# Arduino_Shield.net
KiCad netlist of a schematic drawn in EAGLE
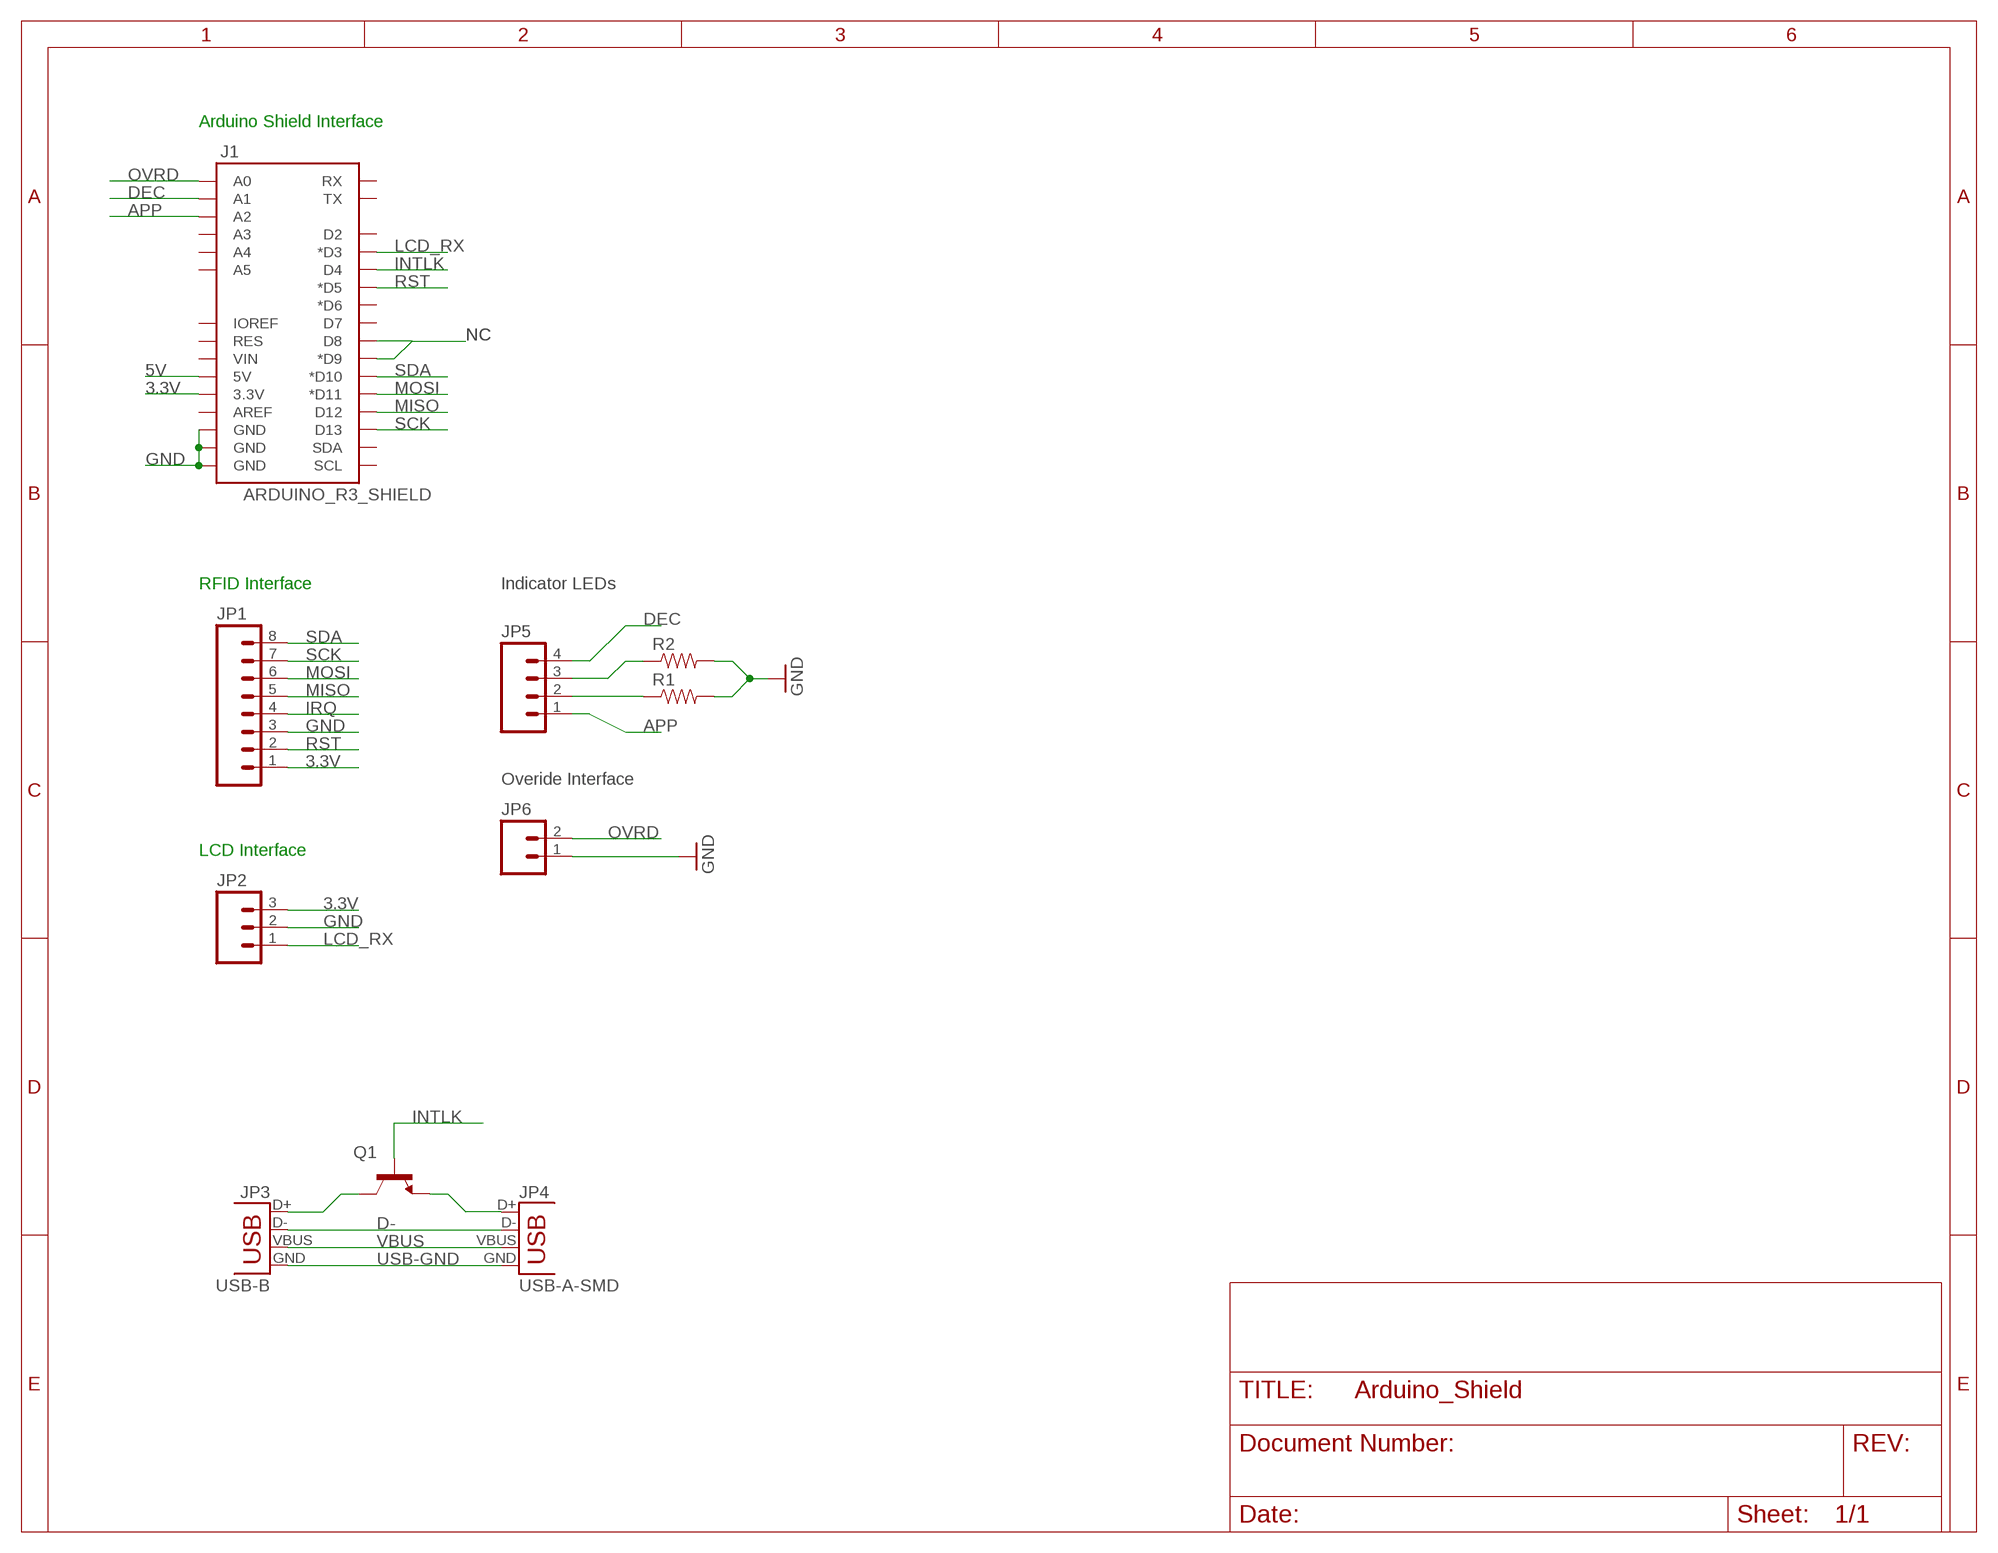
[diagram p0: schematic, sheet 1]

(export (version "E")
  (design (tool "Eeschema 10.0.6"))
  (components
    (comp (ref "J1")
      (value "ARDUINO_R3_SHIELD")
      (footprint "eagle-import:UNO_R3_SHIELD")
      (libsource (lib "eagle-import") (part "ARDUINO_R3_SHIELD"))
    )
    (comp (ref "JP1")
      (value "M08LONGPADS")
      (footprint "eagle-import:1X08_LONGPADS")
      (libsource (lib "eagle-import") (part "M08LONGPADS"))
    )
    (comp (ref "JP2")
      (value "M03LONGPADS")
      (footprint "eagle-import:1X03_LONGPADS")
      (libsource (lib "eagle-import") (part "M03LONGPADS"))
    )
    (comp (ref "JP3")
      (value "USB-B")
      (footprint "eagle-import:USB-B-PTH")
      (libsource (lib "eagle-import") (part "USBPTH"))
    )
    (comp (ref "JP4")
      (value "USB-A-SMD")
      (footprint "eagle-import:USB-A-S-NOSILK-FEMALE")
      (libsource (lib "eagle-import") (part "USB-A-SMD"))
    )
    (comp (ref "JP5")
      (value "M04LONGPADS")
      (footprint "eagle-import:1X04_LONGPADS")
      (libsource (lib "eagle-import") (part "M04LONGPADS"))
    )
    (comp (ref "JP6")
      (value "M02LOCK_LONGPADS")
      (footprint "eagle-import:1X02_LOCK_LONGPADS")
      (libsource (lib "eagle-import") (part "M02LOCK_LONGPADS"))
    )
    (comp (ref "Q1")
      (value "TRANSISTOR_NPNBC547")
      (footprint "eagle-import:TO-92-AMMO")
      (libsource (lib "eagle-import") (part "TRANSISTOR_NPNBC547"))
    )
    (comp (ref "R1")
      (value "RESISTORPTH-1/4W")
      (footprint "eagle-import:AXIAL-0.4")
      (libsource (lib "eagle-import") (part "RESISTORPTH-1/4W"))
    )
    (comp (ref "R2")
      (value "RESISTORPTH-1/4W")
      (footprint "eagle-import:AXIAL-0.4")
      (libsource (lib "eagle-import") (part "RESISTORPTH-1/4W"))
    )
  )
  (nets
    (net (code "1") (name "/3.3V") (class "Default")
      (node (ref "J1") (pin "3.3V") (pinfunction "3.3V_3.3V") (pintype "bidirectional"))
      (node (ref "JP1") (pin "1") (pinfunction "1_1") (pintype "passive"))
      (node (ref "JP2") (pin "3") (pinfunction "3_3") (pintype "passive"))
    )
    (net (code "2") (name "/5V") (class "Default")
      (node (ref "J1") (pin "5V") (pinfunction "5V_5V") (pintype "bidirectional"))
    )
    (net (code "3") (name "/APP") (class "Default")
      (node (ref "J1") (pin "A2") (pinfunction "A2_A2") (pintype "bidirectional"))
      (node (ref "JP5") (pin "1") (pinfunction "1_1") (pintype "passive"))
    )
    (net (code "4") (name "/D-") (class "Default")
      (node (ref "JP3") (pin "D-") (pinfunction "D-_D-") (pintype "bidirectional"))
      (node (ref "JP4") (pin "D-") (pinfunction "D-_D-") (pintype "bidirectional"))
    )
    (net (code "5") (name "/DEC") (class "Default")
      (node (ref "J1") (pin "A1") (pinfunction "A1_A1") (pintype "bidirectional"))
      (node (ref "JP5") (pin "4") (pinfunction "4_4") (pintype "passive"))
    )
    (net (code "6") (name "/INTLK") (class "Default")
      (node (ref "J1") (pin "D4") (pinfunction "D4_D4") (pintype "bidirectional"))
      (node (ref "Q1") (pin "2") (pinfunction "B_2") (pintype "passive"))
    )
    (net (code "7") (name "/IRQ") (class "Default")
      (node (ref "JP1") (pin "4") (pinfunction "4_4") (pintype "passive"))
    )
    (net (code "8") (name "/LCD_RX") (class "Default")
      (node (ref "J1") (pin "D3") (pinfunction "*D3_D3") (pintype "bidirectional"))
      (node (ref "JP2") (pin "1") (pinfunction "1_1") (pintype "passive"))
    )
    (net (code "9") (name "/MISO") (class "Default")
      (node (ref "J1") (pin "D12") (pinfunction "D12_D12") (pintype "bidirectional"))
      (node (ref "JP1") (pin "5") (pinfunction "5_5") (pintype "passive"))
    )
    (net (code "10") (name "/MOSI") (class "Default")
      (node (ref "J1") (pin "D11") (pinfunction "*D11_D11") (pintype "bidirectional"))
      (node (ref "JP1") (pin "6") (pinfunction "6_6") (pintype "passive"))
    )
    (net (code "11") (name "/OVRD") (class "Default")
      (node (ref "J1") (pin "A0") (pinfunction "A0_A0") (pintype "bidirectional"))
      (node (ref "JP6") (pin "2") (pinfunction "2_2") (pintype "passive"))
    )
    (net (code "12") (name "/RST") (class "Default")
      (node (ref "J1") (pin "D5") (pinfunction "*D5_D5") (pintype "bidirectional"))
      (node (ref "JP1") (pin "2") (pinfunction "2_2") (pintype "passive"))
    )
    (net (code "13") (name "/SCK") (class "Default")
      (node (ref "J1") (pin "D13") (pinfunction "D13_D13") (pintype "bidirectional"))
      (node (ref "JP1") (pin "7") (pinfunction "7_7") (pintype "passive"))
    )
    (net (code "14") (name "/SDA") (class "Default")
      (node (ref "J1") (pin "D10") (pinfunction "*D10_D10") (pintype "bidirectional"))
      (node (ref "JP1") (pin "8") (pinfunction "8_8") (pintype "passive"))
    )
    (net (code "15") (name "/USB-GND") (class "Default")
      (node (ref "JP3") (pin "GND") (pinfunction "GND_GND") (pintype "bidirectional"))
      (node (ref "JP4") (pin "GND") (pinfunction "GND_GND") (pintype "bidirectional"))
    )
    (net (code "16") (name "/VBUS") (class "Default")
      (node (ref "JP3") (pin "VBUS") (pinfunction "VBUS_VBUS") (pintype "bidirectional"))
      (node (ref "JP4") (pin "VBUS") (pinfunction "VBUS_VBUS") (pintype "bidirectional"))
    )
    (net (code "17") (name "GND") (class "Default")
      (node (ref "J1") (pin "GND@0") (pinfunction "GND_GND@0") (pintype "bidirectional"))
      (node (ref "J1") (pin "GND@1") (pinfunction "GND_GND@1") (pintype "bidirectional"))
      (node (ref "J1") (pin "GND@2") (pinfunction "GND_GND@2") (pintype "bidirectional"))
      (node (ref "JP1") (pin "3") (pinfunction "3_3") (pintype "passive"))
      (node (ref "JP2") (pin "2") (pinfunction "2_2") (pintype "passive"))
      (node (ref "JP6") (pin "1") (pinfunction "1_1") (pintype "passive"))
      (node (ref "R1") (pin "P$2") (pinfunction "2_P$2") (pintype "passive"))
      (node (ref "R2") (pin "P$2") (pinfunction "2_P$2") (pintype "passive"))
    )
    (net (code "18") (name "Net-(J1-*D9)") (class "Default")
      (node (ref "J1") (pin "D8") (pinfunction "D8_D8") (pintype "bidirectional"))
      (node (ref "J1") (pin "D9") (pinfunction "*D9_D9") (pintype "bidirectional"))
    )
    (net (code "19") (name "Net-(Q1-C)") (class "Default")
      (node (ref "JP3") (pin "D+") (pinfunction "D+_D+") (pintype "bidirectional"))
      (node (ref "Q1") (pin "1") (pinfunction "C_1") (pintype "passive"))
    )
    (net (code "20") (name "Net-(Q1-E)") (class "Default")
      (node (ref "JP4") (pin "D+") (pinfunction "D+_D+") (pintype "bidirectional"))
      (node (ref "Q1") (pin "3") (pinfunction "E_3") (pintype "passive"))
    )
    (net (code "21") (name "Net-(R1-1)") (class "Default")
      (node (ref "JP5") (pin "2") (pinfunction "2_2") (pintype "passive"))
      (node (ref "R1") (pin "P$1") (pinfunction "1_P$1") (pintype "passive"))
    )
    (net (code "22") (name "Net-(R2-1)") (class "Default")
      (node (ref "JP5") (pin "3") (pinfunction "3_3") (pintype "passive"))
      (node (ref "R2") (pin "P$1") (pinfunction "1_P$1") (pintype "passive"))
    )
    (net (code "23") (name "unconnected-(J1-*D6-PadD6)") (class "Default")
      (node (ref "J1") (pin "D6") (pinfunction "*D6_D6") (pintype "bidirectional"))
    )
    (net (code "24") (name "unconnected-(J1-PadA3)") (class "Default")
      (node (ref "J1") (pin "A3") (pinfunction "A3_A3") (pintype "bidirectional"))
    )
    (net (code "25") (name "unconnected-(J1-PadA4)") (class "Default")
      (node (ref "J1") (pin "A4") (pinfunction "A4_A4") (pintype "bidirectional"))
    )
    (net (code "26") (name "unconnected-(J1-PadA5)") (class "Default")
      (node (ref "J1") (pin "A5") (pinfunction "A5_A5") (pintype "bidirectional"))
    )
    (net (code "27") (name "unconnected-(J1-PadAREF)") (class "Default")
      (node (ref "J1") (pin "AREF") (pinfunction "AREF_AREF") (pintype "bidirectional"))
    )
    (net (code "28") (name "unconnected-(J1-PadD2)") (class "Default")
      (node (ref "J1") (pin "D2") (pinfunction "D2_D2") (pintype "bidirectional"))
    )
    (net (code "29") (name "unconnected-(J1-PadD7)") (class "Default")
      (node (ref "J1") (pin "D7") (pinfunction "D7_D7") (pintype "bidirectional"))
    )
    (net (code "30") (name "unconnected-(J1-PadIOREF)") (class "Default")
      (node (ref "J1") (pin "IOREF") (pinfunction "IOREF_IOREF") (pintype "bidirectional"))
    )
    (net (code "31") (name "unconnected-(J1-PadRES)") (class "Default")
      (node (ref "J1") (pin "RES") (pinfunction "RES_RES") (pintype "bidirectional"))
    )
    (net (code "32") (name "unconnected-(J1-PadRX)") (class "Default")
      (node (ref "J1") (pin "RX") (pinfunction "RX_RX") (pintype "bidirectional"))
    )
    (net (code "33") (name "unconnected-(J1-PadSCL)") (class "Default")
      (node (ref "J1") (pin "SCL") (pinfunction "SCL_SCL") (pintype "bidirectional"))
    )
    (net (code "34") (name "unconnected-(J1-PadSDA)") (class "Default")
      (node (ref "J1") (pin "SDA") (pinfunction "SDA_SDA") (pintype "bidirectional"))
    )
    (net (code "35") (name "unconnected-(J1-PadTX)") (class "Default")
      (node (ref "J1") (pin "TX") (pinfunction "TX_TX") (pintype "bidirectional"))
    )
    (net (code "36") (name "unconnected-(J1-PadVIN)") (class "Default")
      (node (ref "J1") (pin "VIN") (pinfunction "VIN_VIN") (pintype "bidirectional"))
    )
  )
)
